# DoorControllerv2.net
KiCad netlist of a schematic drawn in Altium Designer
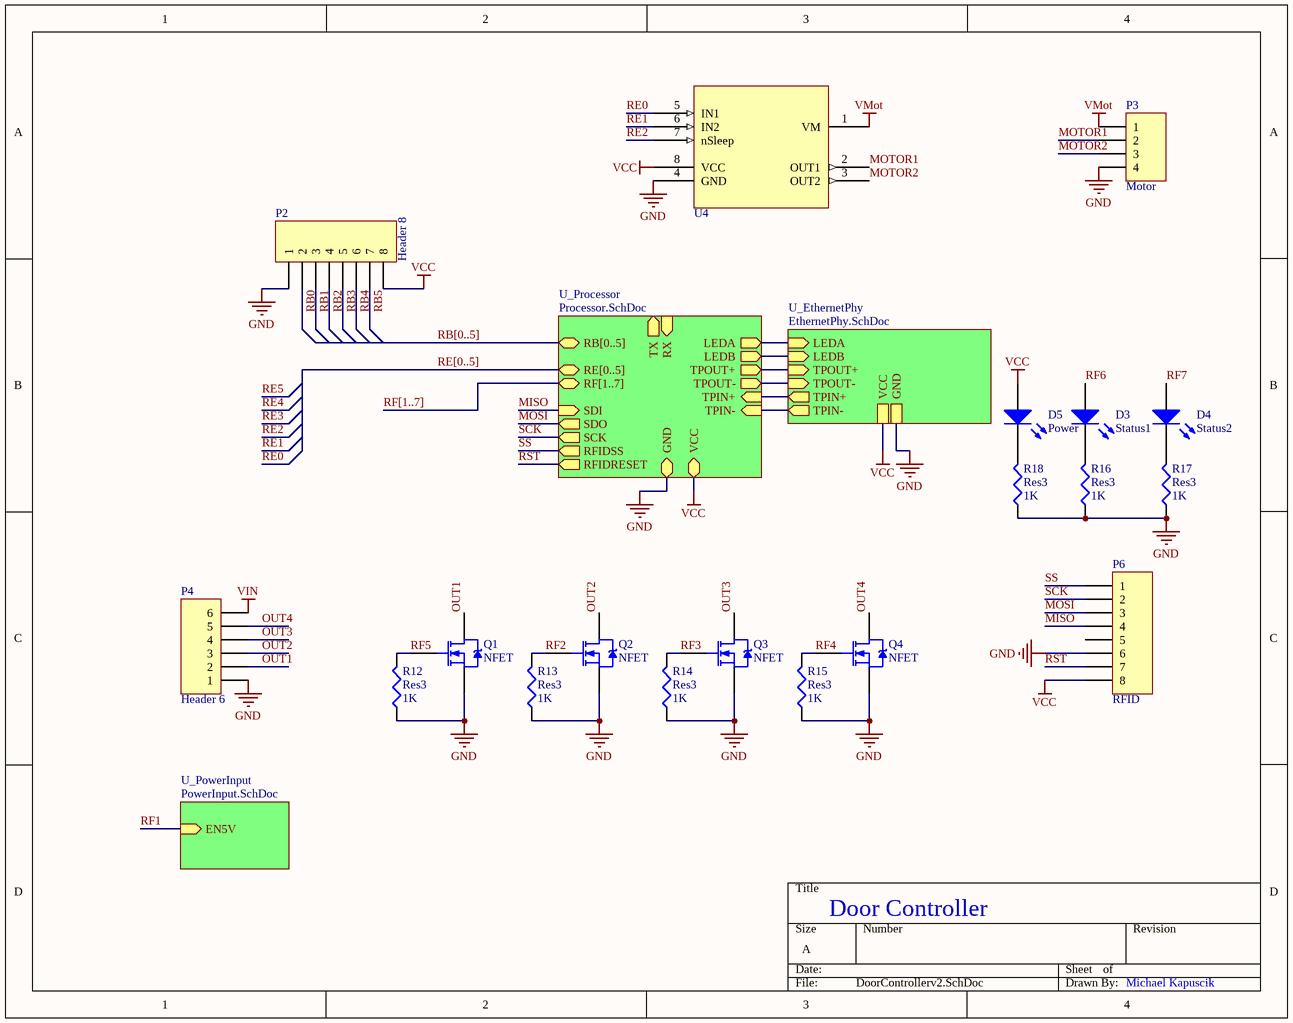
[diagram p0: DoorControllerv2.SchDoc]

(export (version "E")
  (design (tool "Eeschema 10.0.6"))
  (components
    (comp (ref "D3")
      (value "Status1")
      (footprint "0603 LED")
      (description "Typical INFRARED GaAs LED")
      (fields (field (name "PUBLISHER") "Altium Limited"))
      (libsource (lib "Miscellaneous Devices") (part "LED0"))
    )
    (comp (ref "D4")
      (value "Status2")
      (footprint "0603 LED")
      (description "Typical INFRARED GaAs LED")
      (fields (field (name "PUBLISHER") "Altium Limited"))
      (libsource (lib "Miscellaneous Devices") (part "LED0"))
    )
    (comp (ref "D5")
      (value "Power")
      (footprint "0603 LED")
      (description "Typical INFRARED GaAs LED")
      (fields (field (name "PUBLISHER") "Altium Limited"))
      (libsource (lib "Miscellaneous Devices") (part "LED0"))
    )
    (comp (ref "P2")
      (value "Header 8")
      (footprint "HDR1X8")
      (description "Header, 8-Pin")
      (fields (field (name "PUBLISHER") "Altium Limited"))
      (libsource (lib "Miscellaneous Connectors") (part "Header 8"))
    )
    (comp (ref "P3")
      (value "Motor")
      (footprint "HDR1X4")
      (description "Header, 4-Pin")
      (fields (field (name "PUBLISHER") "Altium Limited"))
      (libsource (lib "Miscellaneous Connectors") (part "Header 4"))
    )
    (comp (ref "P4")
      (value "Header 6")
      (footprint "HDR1X6")
      (description "Header, 6-Pin")
      (fields (field (name "PUBLISHER") "Altium Limited"))
      (libsource (lib "Miscellaneous Connectors") (part "Header 6"))
    )
    (comp (ref "P6")
      (value "RFID")
      (footprint "HDR1X8")
      (description "Header, 8-Pin")
      (fields (field (name "PUBLISHER") "Altium Limited"))
      (libsource (lib "") (part "Header 8_1"))
    )
    (comp (ref "Q1")
      (value "NFET")
      (footprint "SOT-23_M")
      (description "30V 3.4A N channel HEXFET")
      (libsource (lib "Miscellaneous Devices") (part "AO3418"))
    )
    (comp (ref "Q2")
      (value "NFET")
      (footprint "SOT-23_M")
      (description "30V 3.4A N channel HEXFET")
      (libsource (lib "Miscellaneous Devices") (part "AO3418"))
    )
    (comp (ref "Q3")
      (value "NFET")
      (footprint "SOT-23_M")
      (description "30V 3.4A N channel HEXFET")
      (libsource (lib "Miscellaneous Devices") (part "AO3418"))
    )
    (comp (ref "Q4")
      (value "NFET")
      (footprint "SOT-23_M")
      (description "30V 3.4A N channel HEXFET")
      (libsource (lib "Miscellaneous Devices") (part "AO3418"))
    )
    (comp (ref "R12")
      (value "Res3")
      (footprint "J1-0603")
      (description "Resistor")
      (fields (field (name "ALTIUM_VALUE") "1K") (field (name "PUBLISHER") "Altium Limited"))
      (libsource (lib "Miscellaneous Devices") (part "Res3"))
    )
    (comp (ref "R13")
      (value "Res3")
      (footprint "J1-0603")
      (description "Resistor")
      (fields (field (name "ALTIUM_VALUE") "1K") (field (name "PUBLISHER") "Altium Limited"))
      (libsource (lib "Miscellaneous Devices") (part "Res3"))
    )
    (comp (ref "R14")
      (value "Res3")
      (footprint "J1-0603")
      (description "Resistor")
      (fields (field (name "ALTIUM_VALUE") "1K") (field (name "PUBLISHER") "Altium Limited"))
      (libsource (lib "Miscellaneous Devices") (part "Res3"))
    )
    (comp (ref "R15")
      (value "Res3")
      (footprint "J1-0603")
      (description "Resistor")
      (fields (field (name "ALTIUM_VALUE") "1K") (field (name "PUBLISHER") "Altium Limited"))
      (libsource (lib "Miscellaneous Devices") (part "Res3"))
    )
    (comp (ref "R16")
      (value "Res3")
      (footprint "J1-0603")
      (description "Resistor")
      (fields (field (name "ALTIUM_VALUE") "1K") (field (name "PUBLISHER") "Altium Limited"))
      (libsource (lib "Miscellaneous Devices") (part "Res3"))
    )
    (comp (ref "R17")
      (value "Res3")
      (footprint "J1-0603")
      (description "Resistor")
      (fields (field (name "ALTIUM_VALUE") "1K") (field (name "PUBLISHER") "Altium Limited"))
      (libsource (lib "Miscellaneous Devices") (part "Res3"))
    )
    (comp (ref "R18")
      (value "Res3")
      (footprint "J1-0603")
      (description "Resistor")
      (fields (field (name "ALTIUM_VALUE") "1K") (field (name "PUBLISHER") "Altium Limited"))
      (libsource (lib "Miscellaneous Devices") (part "Res3"))
    )
    (comp (ref "U4")
      (value "1.8A H-Bridge")
      (footprint "S-PWSON-N8")
      (description "1.8A H0bridge with integrated motor drive FETs")
      (libsource (lib "Miscellaneous Devices") (part "DRV8837 H-Bridge"))
    )
  )
  (nets
    (net (code "3") (name "/MISO") (class "Default")
      (node (ref "P6") (pin "4") (pinfunction "4_4") (pintype "passive"))
    )
    (net (code "4") (name "/MOSI") (class "Default")
      (node (ref "P6") (pin "3") (pinfunction "3_3") (pintype "passive"))
    )
    (net (code "5") (name "/MOTOR1") (class "Default")
      (node (ref "P3") (pin "2") (pinfunction "2_2") (pintype "passive"))
      (node (ref "U4") (pin "2") (pinfunction "OUT1_2") (pintype "output"))
    )
    (net (code "6") (name "/MOTOR2") (class "Default")
      (node (ref "P3") (pin "3") (pinfunction "3_3") (pintype "passive"))
      (node (ref "U4") (pin "3") (pinfunction "OUT2_3") (pintype "output"))
    )
    (net (code "7") (name "/OUT1") (class "Default")
      (node (ref "P4") (pin "2") (pinfunction "2_2") (pintype "passive"))
      (node (ref "Q1") (pin "3") (pinfunction "D_3") (pintype "passive"))
    )
    (net (code "8") (name "/OUT2") (class "Default")
      (node (ref "P4") (pin "3") (pinfunction "3_3") (pintype "passive"))
      (node (ref "Q2") (pin "3") (pinfunction "D_3") (pintype "passive"))
    )
    (net (code "9") (name "/OUT3") (class "Default")
      (node (ref "P4") (pin "4") (pinfunction "4_4") (pintype "passive"))
      (node (ref "Q3") (pin "3") (pinfunction "D_3") (pintype "passive"))
    )
    (net (code "10") (name "/OUT4") (class "Default")
      (node (ref "P4") (pin "5") (pinfunction "5_5") (pintype "passive"))
      (node (ref "Q4") (pin "3") (pinfunction "D_3") (pintype "passive"))
    )
    (net (code "11") (name "/RB0") (class "Default")
      (node (ref "P2") (pin "2") (pinfunction "2_2") (pintype "passive"))
    )
    (net (code "12") (name "/RB1") (class "Default")
      (node (ref "P2") (pin "3") (pinfunction "3_3") (pintype "passive"))
    )
    (net (code "13") (name "/RB2") (class "Default")
      (node (ref "P2") (pin "4") (pinfunction "4_4") (pintype "passive"))
    )
    (net (code "14") (name "/RB3") (class "Default")
      (node (ref "P2") (pin "5") (pinfunction "5_5") (pintype "passive"))
    )
    (net (code "15") (name "/RB4") (class "Default")
      (node (ref "P2") (pin "6") (pinfunction "6_6") (pintype "passive"))
    )
    (net (code "16") (name "/RB5") (class "Default")
      (node (ref "P2") (pin "7") (pinfunction "7_7") (pintype "passive"))
    )
    (net (code "18") (name "/RE0") (class "Default")
      (node (ref "U4") (pin "5") (pinfunction "IN1_5") (pintype "input"))
    )
    (net (code "19") (name "/RE1") (class "Default")
      (node (ref "U4") (pin "6") (pinfunction "IN2_6") (pintype "input"))
    )
    (net (code "20") (name "/RE2") (class "Default")
      (node (ref "U4") (pin "7") (pinfunction "nSleep_7") (pintype "input"))
    )
    (net (code "26") (name "/RF2") (class "Default")
      (node (ref "Q2") (pin "1") (pinfunction "G_1") (pintype "passive"))
      (node (ref "R13") (pin "2") (pinfunction "2_2") (pintype "passive"))
    )
    (net (code "27") (name "/RF3") (class "Default")
      (node (ref "Q3") (pin "1") (pinfunction "G_1") (pintype "passive"))
      (node (ref "R14") (pin "2") (pinfunction "2_2") (pintype "passive"))
    )
    (net (code "28") (name "/RF4") (class "Default")
      (node (ref "Q4") (pin "1") (pinfunction "G_1") (pintype "passive"))
      (node (ref "R15") (pin "2") (pinfunction "2_2") (pintype "passive"))
    )
    (net (code "29") (name "/RF5") (class "Default")
      (node (ref "Q1") (pin "1") (pinfunction "G_1") (pintype "passive"))
      (node (ref "R12") (pin "2") (pinfunction "2_2") (pintype "passive"))
    )
    (net (code "30") (name "/RF6") (class "Default")
      (node (ref "D3") (pin "1") (pinfunction "A_1") (pintype "passive"))
    )
    (net (code "31") (name "/RF7") (class "Default")
      (node (ref "D4") (pin "1") (pinfunction "A_1") (pintype "passive"))
    )
    (net (code "33") (name "/RST") (class "Default")
      (node (ref "P6") (pin "7") (pinfunction "7_7") (pintype "passive"))
    )
    (net (code "35") (name "/SCK") (class "Default")
      (node (ref "P6") (pin "2") (pinfunction "2_2") (pintype "passive"))
    )
    (net (code "36") (name "/SS") (class "Default")
      (node (ref "P6") (pin "1") (pinfunction "1_1") (pintype "passive"))
    )
    (net (code "42") (name "GND") (class "Default")
      (node (ref "P2") (pin "1") (pinfunction "1_1") (pintype "passive"))
      (node (ref "P3") (pin "4") (pinfunction "4_4") (pintype "passive"))
      (node (ref "P4") (pin "1") (pinfunction "1_1") (pintype "passive"))
      (node (ref "P6") (pin "6") (pinfunction "6_6") (pintype "passive"))
      (node (ref "Q1") (pin "2") (pinfunction "S_2") (pintype "passive"))
      (node (ref "Q2") (pin "2") (pinfunction "S_2") (pintype "passive"))
      (node (ref "Q3") (pin "2") (pinfunction "S_2") (pintype "passive"))
      (node (ref "Q4") (pin "2") (pinfunction "S_2") (pintype "passive"))
      (node (ref "R12") (pin "1") (pinfunction "1_1") (pintype "passive"))
      (node (ref "R13") (pin "1") (pinfunction "1_1") (pintype "passive"))
      (node (ref "R14") (pin "1") (pinfunction "1_1") (pintype "passive"))
      (node (ref "R15") (pin "1") (pinfunction "1_1") (pintype "passive"))
      (node (ref "R16") (pin "1") (pinfunction "1_1") (pintype "passive"))
      (node (ref "R17") (pin "1") (pinfunction "1_1") (pintype "passive"))
      (node (ref "R18") (pin "1") (pinfunction "1_1") (pintype "passive"))
      (node (ref "U4") (pin "4") (pinfunction "GND_4") (pintype "power_in"))
    )
    (net (code "43") (name "Net-(D3-K)") (class "Default")
      (node (ref "D3") (pin "2") (pinfunction "K_2") (pintype "passive"))
      (node (ref "R16") (pin "2") (pinfunction "2_2") (pintype "passive"))
    )
    (net (code "44") (name "Net-(D4-K)") (class "Default")
      (node (ref "D4") (pin "2") (pinfunction "K_2") (pintype "passive"))
      (node (ref "R17") (pin "2") (pinfunction "2_2") (pintype "passive"))
    )
    (net (code "45") (name "Net-(D5-K)") (class "Default")
      (node (ref "D5") (pin "2") (pinfunction "K_2") (pintype "passive"))
      (node (ref "R18") (pin "2") (pinfunction "2_2") (pintype "passive"))
    )
    (net (code "46") (name "VCC") (class "Default")
      (node (ref "D5") (pin "1") (pinfunction "A_1") (pintype "passive"))
      (node (ref "P2") (pin "8") (pinfunction "8_8") (pintype "passive"))
      (node (ref "P6") (pin "8") (pinfunction "8_8") (pintype "passive"))
      (node (ref "U4") (pin "8") (pinfunction "VCC_8") (pintype "power_in"))
    )
    (net (code "47") (name "VIN") (class "Default")
      (node (ref "P4") (pin "6") (pinfunction "6_6") (pintype "passive"))
    )
    (net (code "48") (name "VMot") (class "Default")
      (node (ref "P3") (pin "1") (pinfunction "1_1") (pintype "passive"))
      (node (ref "U4") (pin "1") (pinfunction "VM_1") (pintype "power_in"))
    )
    (net (code "49") (name "unconnected-(P6-Pad5)") (class "Default")
      (node (ref "P6") (pin "5") (pinfunction "5_5") (pintype "passive"))
    )
  )
)
